# B1S.net
KiCad netlist of a schematic drawn in EasyEDA Pro
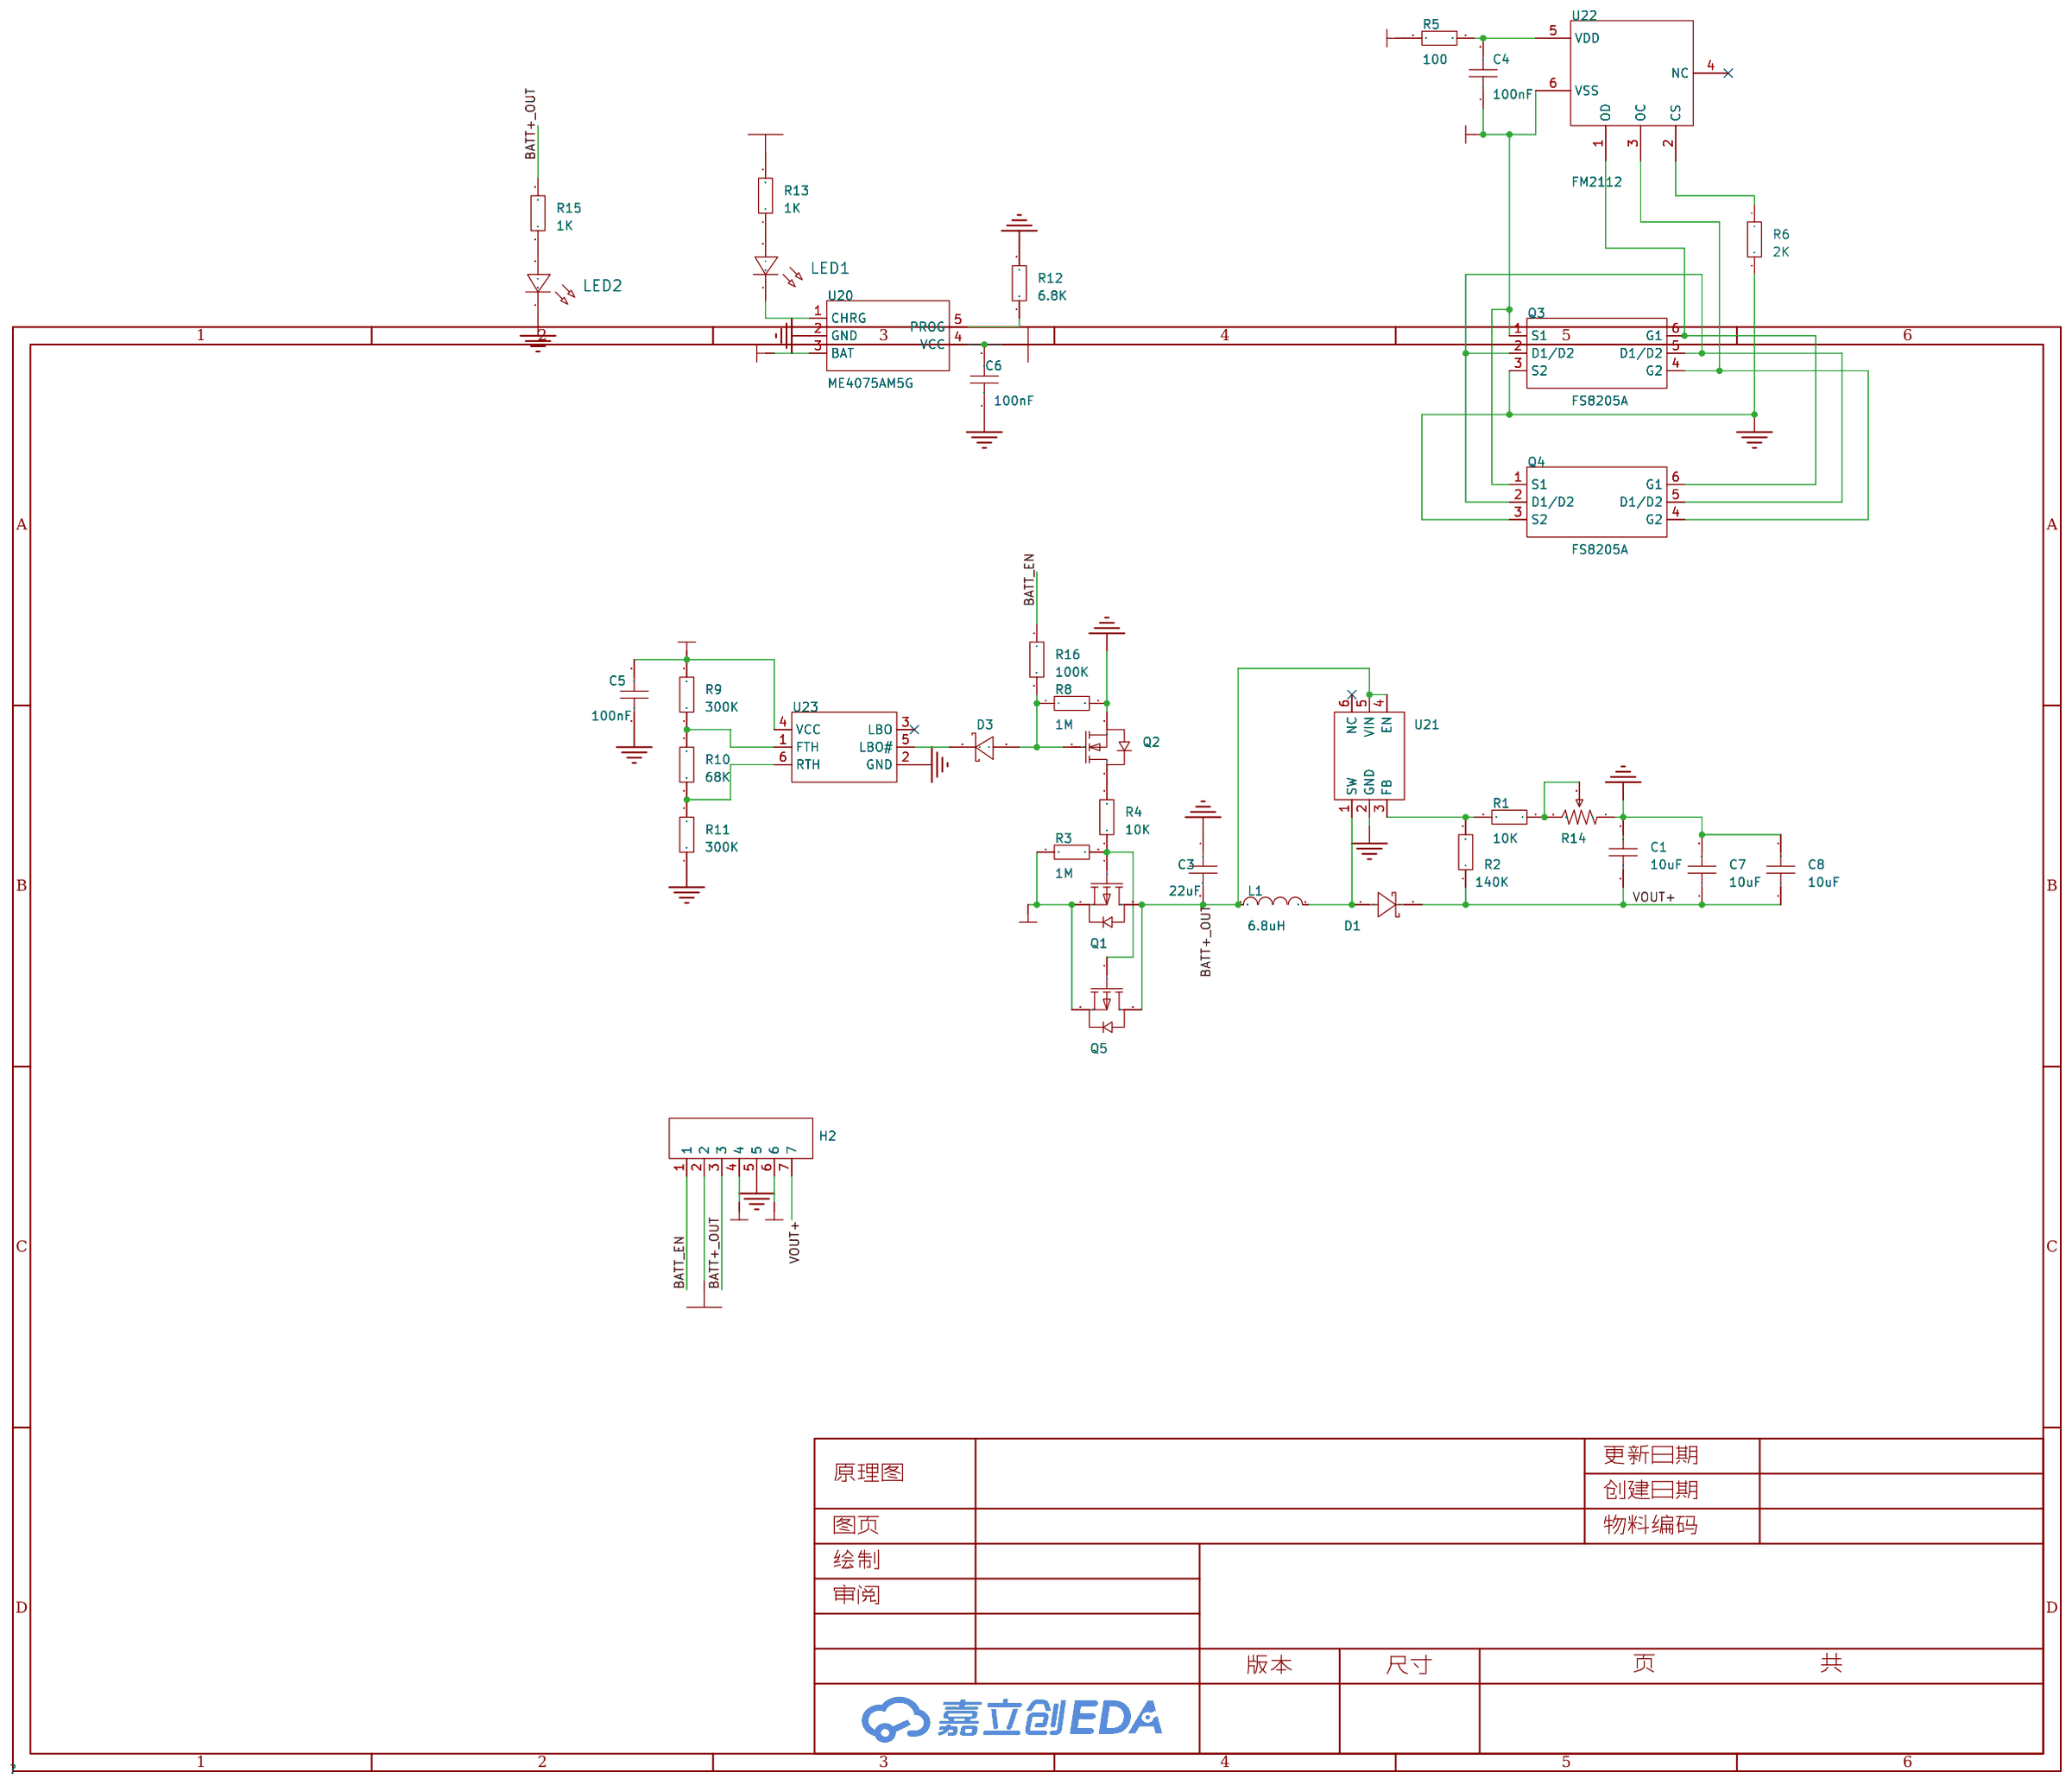
[diagram p0: schematic sheet]

(export (version "E")
  (design (tool "Eeschema 10.0.6"))
  (components
    (comp (ref "C1")
      (value "10uF")
      (footprint "easyedapro:C0805")
      (libsource (lib "easyedapro") (part "CapAcitance"))
    )
    (comp (ref "C3")
      (value "22uF")
      (footprint "easyedapro:C0805")
      (libsource (lib "easyedapro") (part "CapAcitance"))
    )
    (comp (ref "C4")
      (value "100nF")
      (footprint "easyedapro:C0805")
      (libsource (lib "easyedapro") (part "CapAcitance"))
    )
    (comp (ref "C5")
      (value "100nF")
      (footprint "easyedapro:C0805")
      (libsource (lib "easyedapro") (part "CapAcitance"))
    )
    (comp (ref "C6")
      (value "100nF")
      (footprint "easyedapro:C0805")
      (libsource (lib "easyedapro") (part "CapAcitance"))
    )
    (comp (ref "C7")
      (value "10uF")
      (footprint "easyedapro:C0805")
      (libsource (lib "easyedapro") (part "CapAcitance"))
    )
    (comp (ref "C8")
      (value "10uF")
      (footprint "easyedapro:C0805")
      (libsource (lib "easyedapro") (part "CapAcitance"))
    )
    (comp (ref "D1")
      (value "SS34")
      (footprint "easyedapro:SMA_L4.3-W2.6-LS5.0-FD")
      (description "二极管配置:独立式;正向压降(Vf):550mV@3.0A;直流反向耐压(Vr):40V;整流电流:3A;")
      (fields (field (name "Manufacturer") "R+O(宏嘉诚)"))
      (libsource (lib "easyedapro") (part "SS34_C7420365"))
    )
    (comp (ref "D3")
      (value "1N5819WS")
      (footprint "easyedapro:SOD-323_L1.8-W1.3-LS2.5-RD")
      (description "正向压降(Vf):600mV@1A;直流反向耐压(Vr):40V;整流电流:1A;")
      (fields (field (name "Manufacturer") "Hottech(合科泰)"))
      (libsource (lib "easyedapro") (part "1N5819WS"))
    )
    (comp (ref "H2")
      (value "~")
      (footprint "easyedapro:HDR-TH_7P-P2.54-V-F")
      (libsource (lib "easyedapro") (part "220S-1*7P H=8.5MM Ytype Gold-plated"))
    )
    (comp (ref "L1")
      (value "6.8uH")
      (footprint "easyedapro:IND-SMD_L7.0-W6.6")
      (description "电感值:6.8uH;精度:±20%;额定电流:5A;饱和电流(Isat):6A;类型:一体成型电感;")
      (fields (field (name "Manufacturer Part") "FXL0630-6R8-M") (field (name "Manufacturer") "cjiang(长江微电)"))
      (libsource (lib "easyedapro") (part "FXL0630-6R8-M"))
    )
    (comp (ref "LED1")
      (value "~")
      (footprint "easyedapro:LED_0603")
      (libsource (lib "easyedapro") (part "LED_R"))
    )
    (comp (ref "LED2")
      (value "~")
      (footprint "easyedapro:LED_0603")
      (libsource (lib "easyedapro") (part "LED_R"))
    )
    (comp (ref "Q1")
      (value "SI2305CDS-T1-GE3")
      (footprint "easyedapro:SOT-23-3_L2.9-W1.3-P1.90-LS2.4-BR")
      (fields (field (name "Manufacturer") "VISHAY(威世)"))
      (libsource (lib "easyedapro") (part "SI2305CDS-T1-GE3"))
    )
    (comp (ref "Q2")
      (value "SI2302")
      (footprint "easyedapro:SOT-23-3_L2.9-W1.3-P1.90-LS2.4-BR")
      (description "数量:1个N沟道;漏源电压(Vdss):20V;连续漏极电流(Id):3A;导通电阻(RDS(on)):65mΩ@2.5V;耗散功率(Pd):1W;阈值电压(Vgs(th)):1V@250uA;")
      (fields (field (name "Manufacturer") "YONGYUTAI(永裕泰)"))
      (libsource (lib "easyedapro") (part "SI2302_C2891732"))
    )
    (comp (ref "Q3")
      (value "FS8205A")
      (footprint "easyedapro:SOT-23-6_L2.9-W1.6-P0.95-LS2.8-BR")
      (description "类型:2个N沟道;漏源电压(Vdss):20V;连续漏极电流(Id):6A;导通电阻(RDS(on)):18mΩ@4.5V,6A;耗散功率(Pd):1.5W;阈值电压(Vgs(th)):1.2V;")
      (fields (field (name "Manufacturer") "FUXINSEMI(富芯森美)"))
      (libsource (lib "easyedapro") (part "FS8205A_C908265"))
    )
    (comp (ref "Q4")
      (value "FS8205A")
      (footprint "easyedapro:SOT-23-6_L2.9-W1.6-P0.95-LS2.8-BR")
      (description "类型:2个N沟道;漏源电压(Vdss):20V;连续漏极电流(Id):6A;导通电阻(RDS(on)):18mΩ@4.5V,6A;耗散功率(Pd):1.5W;阈值电压(Vgs(th)):1.2V;")
      (fields (field (name "Manufacturer") "FUXINSEMI(富芯森美)"))
      (libsource (lib "easyedapro") (part "FS8205A_C908265"))
    )
    (comp (ref "Q5")
      (value "SI2305CDS-T1-GE3")
      (footprint "easyedapro:SOT-23-3_L2.9-W1.3-P1.90-LS2.4-BR")
      (fields (field (name "Manufacturer") "VISHAY(威世)"))
      (libsource (lib "easyedapro") (part "SI2305CDS-T1-GE3"))
    )
    (comp (ref "R1") (value "10K") (footprint "easyedapro:R0603") (libsource (lib "easyedapro") (part "电阻")))
    (comp (ref "R2") (value "140K") (footprint "easyedapro:R0603") (libsource (lib "easyedapro") (part "电阻")))
    (comp (ref "R3") (value "1M") (footprint "easyedapro:R0603") (libsource (lib "easyedapro") (part "电阻")))
    (comp (ref "R4") (value "10K") (footprint "easyedapro:R0603") (libsource (lib "easyedapro") (part "电阻")))
    (comp (ref "R5") (value "100") (footprint "easyedapro:R0603") (libsource (lib "easyedapro") (part "电阻")))
    (comp (ref "R6") (value "2K") (footprint "easyedapro:R0603") (libsource (lib "easyedapro") (part "电阻")))
    (comp (ref "R8") (value "1M") (footprint "easyedapro:R0603") (libsource (lib "easyedapro") (part "电阻")))
    (comp (ref "R9") (value "300K") (footprint "easyedapro:R0603") (libsource (lib "easyedapro") (part "电阻")))
    (comp (ref "R10") (value "68K") (footprint "easyedapro:R0603") (libsource (lib "easyedapro") (part "电阻")))
    (comp (ref "R11")
      (value "300K")
      (footprint "easyedapro:R0603")
      (libsource (lib "easyedapro") (part "电阻"))
    )
    (comp (ref "R12")
      (value "6.8K")
      (footprint "easyedapro:R0603")
      (libsource (lib "easyedapro") (part "电阻"))
    )
    (comp (ref "R13") (value "1K") (footprint "easyedapro:R0603") (libsource (lib "easyedapro") (part "电阻")))
    (comp (ref "R14")
      (value "500kΩ")
      (footprint "easyedapro:RES-ADJ-SMD_JER33X-1-14")
      (description "阻值:500kΩ;精度:±25%;功率:150mW;温度系数:±250ppm/°C;")
      (fields (field (name "Manufacturer Part") "JER33X-1-55") (field (name "Manufacturer") "JIERR(捷而瑞)"))
      (libsource (lib "easyedapro") (part "JER33X-1-55"))
    )
    (comp (ref "R15") (value "1K") (footprint "easyedapro:R0603") (libsource (lib "easyedapro") (part "电阻")))
    (comp (ref "R16")
      (value "100K")
      (footprint "easyedapro:R0603")
      (libsource (lib "easyedapro") (part "电阻"))
    )
    (comp (ref "U20")
      (value "ME4075AM5G")
      (footprint "easyedapro:SOT-23-5_L2.9-W1.6-P0.95-LS2.8-BL")
      (fields (field (name "Manufacturer") "MICRONE(南京微盟)"))
      (libsource (lib "easyedapro") (part "ME4075AM5G"))
    )
    (comp (ref "U21")
      (value "SX1308")
      (footprint "easyedapro:SOT-23-6_L2.9-W1.6-P0.95-LS2.8-BL")
      (description "功能类型:升压型;输出类型:可调;工作电压:2V~24V;输出电压:28V;输出电流:2A;")
      (fields (field (name "Manufacturer") "SX(硕芯科技)"))
      (libsource (lib "easyedapro") (part "SX1308"))
    )
    (comp (ref "U22")
      (value "FM2112")
      (footprint "easyedapro:SOT-23-6_L2.9-W1.6-P0.95-LS2.8-BL")
      (fields (field (name "Manufacturer") "FM(富满)"))
      (libsource (lib "easyedapro") (part "FM2112"))
    )
    (comp (ref "U23")
      (value "CN312")
      (footprint "easyedapro:SOT-23-6_L2.9-W1.6-P0.95-LS2.8-BL")
      (description "集成电路")
      (fields (field (name "Manufacturer") "CONSONANCE(上海如韵)"))
      (libsource (lib "easyedapro") (part "CN312"))
    )
  )
  (nets
    (net (code "1") (name "/BATT+_OUT") (class "Default")
      (node (ref "C3") (pin "2") (pinfunction "2_2") (pintype "input"))
      (node (ref "H2") (pin "3") (pinfunction "3_3") (pintype "unspecified"))
      (node (ref "L1") (pin "1") (pinfunction "1_1") (pintype "unspecified"))
      (node (ref "Q1") (pin "3") (pinfunction "D_3") (pintype "unspecified"))
      (node (ref "Q5") (pin "3") (pinfunction "D_3") (pintype "unspecified"))
      (node (ref "R15") (pin "2") (pinfunction "2_2") (pintype "input"))
      (node (ref "U21") (pin "4") (pinfunction "EN_4") (pintype "unspecified"))
      (node (ref "U21") (pin "5") (pinfunction "VIN_5") (pintype "unspecified"))
    )
    (net (code "2") (name "/BATT_EN") (class "Default")
      (node (ref "H2") (pin "1") (pinfunction "1_1") (pintype "unspecified"))
      (node (ref "R16") (pin "1") (pinfunction "1_1") (pintype "input"))
    )
    (net (code "3") (name "/VOUT+") (class "Default")
      (node (ref "C1") (pin "1") (pinfunction "1_1") (pintype "input"))
      (node (ref "C7") (pin "1") (pinfunction "1_1") (pintype "input"))
      (node (ref "C8") (pin "1") (pinfunction "1_1") (pintype "input"))
      (node (ref "D1") (pin "2") (pinfunction "K_2") (pintype "unspecified"))
      (node (ref "H2") (pin "7") (pinfunction "7_7") (pintype "unspecified"))
      (node (ref "R2") (pin "1") (pinfunction "1_1") (pintype "input"))
    )
    (net (code "4") (name "BATT+") (class "Default")
      (node (ref "C5") (pin "2") (pinfunction "2_2") (pintype "input"))
      (node (ref "H2") (pin "4") (pinfunction "4_4") (pintype "unspecified"))
      (node (ref "Q1") (pin "2") (pinfunction "S_2") (pintype "unspecified"))
      (node (ref "Q5") (pin "2") (pinfunction "S_2") (pintype "unspecified"))
      (node (ref "R3") (pin "1") (pinfunction "1_1") (pintype "input"))
      (node (ref "R5") (pin "2") (pinfunction "2_2") (pintype "input"))
      (node (ref "R9") (pin "2") (pinfunction "2_2") (pintype "input"))
      (node (ref "U20") (pin "3") (pinfunction "BAT_3") (pintype "unspecified"))
      (node (ref "U23") (pin "4") (pinfunction "VCC_4") (pintype "unspecified"))
    )
    (net (code "5") (name "BATT-") (class "Default")
      (node (ref "C4") (pin "1") (pinfunction "1_1") (pintype "input"))
      (node (ref "H2") (pin "6") (pinfunction "6_6") (pintype "unspecified"))
      (node (ref "Q3") (pin "1") (pinfunction "S1_1") (pintype "unspecified"))
      (node (ref "Q4") (pin "1") (pinfunction "S1_1") (pintype "unspecified"))
      (node (ref "U22") (pin "6") (pinfunction "VSS_6") (pintype "unspecified"))
    )
    (net (code "6") (name "CHG+") (class "Default")
      (node (ref "C6") (pin "2") (pinfunction "2_2") (pintype "input"))
      (node (ref "H2") (pin "2") (pinfunction "2_2") (pintype "unspecified"))
      (node (ref "R13") (pin "2") (pinfunction "2_2") (pintype "input"))
      (node (ref "U20") (pin "4") (pinfunction "VCC_4") (pintype "unspecified"))
    )
    (net (code "7") (name "GND") (class "Default")
      (node (ref "C1") (pin "2") (pinfunction "2_2") (pintype "input"))
      (node (ref "C3") (pin "1") (pinfunction "1_1") (pintype "input"))
      (node (ref "C5") (pin "1") (pinfunction "1_1") (pintype "input"))
      (node (ref "C6") (pin "1") (pinfunction "1_1") (pintype "input"))
      (node (ref "C7") (pin "2") (pinfunction "2_2") (pintype "input"))
      (node (ref "C8") (pin "2") (pinfunction "2_2") (pintype "input"))
      (node (ref "H2") (pin "5") (pinfunction "5_5") (pintype "unspecified"))
      (node (ref "LED2") (pin "1") (pinfunction "C_1") (pintype "input"))
      (node (ref "Q2") (pin "2") (pinfunction "S_2") (pintype "unspecified"))
      (node (ref "Q3") (pin "3") (pinfunction "S2_3") (pintype "unspecified"))
      (node (ref "Q4") (pin "3") (pinfunction "S2_3") (pintype "unspecified"))
      (node (ref "R11") (pin "1") (pinfunction "1_1") (pintype "input"))
      (node (ref "R12") (pin "2") (pinfunction "2_2") (pintype "input"))
      (node (ref "R14") (pin "1") (pinfunction "1_1") (pintype "unspecified"))
      (node (ref "R6") (pin "2") (pinfunction "2_2") (pintype "input"))
      (node (ref "R8") (pin "2") (pinfunction "2_2") (pintype "input"))
      (node (ref "U20") (pin "2") (pinfunction "GND_2") (pintype "unspecified"))
      (node (ref "U21") (pin "2") (pinfunction "GND_2") (pintype "unspecified"))
      (node (ref "U23") (pin "2") (pinfunction "GND_2") (pintype "unspecified"))
    )
    (net (code "8") (name "Net-(D1-A)") (class "Default")
      (node (ref "D1") (pin "1") (pinfunction "A_1") (pintype "unspecified"))
      (node (ref "L1") (pin "2") (pinfunction "2_2") (pintype "unspecified"))
      (node (ref "U21") (pin "1") (pinfunction "SW_1") (pintype "unspecified"))
    )
    (net (code "9") (name "Net-(D3-A)") (class "Default")
      (node (ref "D3") (pin "2") (pinfunction "A_2") (pintype "unspecified"))
      (node (ref "Q2") (pin "1") (pinfunction "G_1") (pintype "unspecified"))
      (node (ref "R16") (pin "2") (pinfunction "2_2") (pintype "input"))
      (node (ref "R8") (pin "1") (pinfunction "1_1") (pintype "input"))
    )
    (net (code "10") (name "Net-(D3-K)") (class "Default")
      (node (ref "D3") (pin "1") (pinfunction "K_1") (pintype "unspecified"))
      (node (ref "U23") (pin "5") (pinfunction "LBO#_5") (pintype "unspecified"))
    )
    (net (code "11") (name "Net-(LED1-A)") (class "Default")
      (node (ref "LED1") (pin "2") (pinfunction "A_2") (pintype "input"))
      (node (ref "R13") (pin "1") (pinfunction "1_1") (pintype "input"))
    )
    (net (code "12") (name "Net-(LED1-C)") (class "Default")
      (node (ref "LED1") (pin "1") (pinfunction "C_1") (pintype "input"))
      (node (ref "U20") (pin "1") (pinfunction "CHRG_1") (pintype "unspecified"))
    )
    (net (code "13") (name "Net-(LED2-A)") (class "Default")
      (node (ref "LED2") (pin "2") (pinfunction "A_2") (pintype "input"))
      (node (ref "R15") (pin "1") (pinfunction "1_1") (pintype "input"))
    )
    (net (code "14") (name "Net-(Q1-G)") (class "Default")
      (node (ref "Q1") (pin "1") (pinfunction "G_1") (pintype "unspecified"))
      (node (ref "Q5") (pin "1") (pinfunction "G_1") (pintype "unspecified"))
      (node (ref "R3") (pin "2") (pinfunction "2_2") (pintype "input"))
      (node (ref "R4") (pin "1") (pinfunction "1_1") (pintype "input"))
    )
    (net (code "15") (name "Net-(Q2-D)") (class "Default")
      (node (ref "Q2") (pin "3") (pinfunction "D_3") (pintype "unspecified"))
      (node (ref "R4") (pin "2") (pinfunction "2_2") (pintype "input"))
    )
    (net (code "16") (name "Net-(Q3-D1{slash}D2-Pad2)") (class "Default")
      (node (ref "Q3") (pin "2") (pinfunction "D1/D2_2") (pintype "unspecified"))
      (node (ref "Q3") (pin "5") (pinfunction "D1/D2_5") (pintype "unspecified"))
      (node (ref "Q4") (pin "2") (pinfunction "D1/D2_2") (pintype "unspecified"))
      (node (ref "Q4") (pin "5") (pinfunction "D1/D2_5") (pintype "unspecified"))
    )
    (net (code "17") (name "Net-(Q3-G1)") (class "Default")
      (node (ref "Q3") (pin "6") (pinfunction "G1_6") (pintype "unspecified"))
      (node (ref "Q4") (pin "6") (pinfunction "G1_6") (pintype "unspecified"))
      (node (ref "U22") (pin "1") (pinfunction "OD_1") (pintype "unspecified"))
    )
    (net (code "18") (name "Net-(Q3-G2)") (class "Default")
      (node (ref "Q3") (pin "4") (pinfunction "G2_4") (pintype "unspecified"))
      (node (ref "Q4") (pin "4") (pinfunction "G2_4") (pintype "unspecified"))
      (node (ref "U22") (pin "3") (pinfunction "OC_3") (pintype "unspecified"))
    )
    (net (code "19") (name "Net-(R1-Pad1)") (class "Default")
      (node (ref "R1") (pin "1") (pinfunction "1_1") (pintype "input"))
      (node (ref "R14") (pin "2") (pinfunction "2_2") (pintype "unspecified"))
      (node (ref "R14") (pin "3") (pinfunction "3_3") (pintype "unspecified"))
    )
    (net (code "20") (name "Net-(U20-PROG)") (class "Default")
      (node (ref "R12") (pin "1") (pinfunction "1_1") (pintype "input"))
      (node (ref "U20") (pin "5") (pinfunction "PROG_5") (pintype "unspecified"))
    )
    (net (code "21") (name "Net-(U21-FB)") (class "Default")
      (node (ref "R1") (pin "2") (pinfunction "2_2") (pintype "input"))
      (node (ref "R2") (pin "2") (pinfunction "2_2") (pintype "input"))
      (node (ref "U21") (pin "3") (pinfunction "FB_3") (pintype "unspecified"))
    )
    (net (code "22") (name "Net-(U22-CS)") (class "Default")
      (node (ref "R6") (pin "1") (pinfunction "1_1") (pintype "input"))
      (node (ref "U22") (pin "2") (pinfunction "CS_2") (pintype "unspecified"))
    )
    (net (code "23") (name "Net-(U22-VDD)") (class "Default")
      (node (ref "C4") (pin "2") (pinfunction "2_2") (pintype "input"))
      (node (ref "R5") (pin "1") (pinfunction "1_1") (pintype "input"))
      (node (ref "U22") (pin "5") (pinfunction "VDD_5") (pintype "unspecified"))
    )
    (net (code "24") (name "Net-(U23-FTH)") (class "Default")
      (node (ref "R10") (pin "2") (pinfunction "2_2") (pintype "input"))
      (node (ref "R9") (pin "1") (pinfunction "1_1") (pintype "input"))
      (node (ref "U23") (pin "1") (pinfunction "FTH_1") (pintype "unspecified"))
    )
    (net (code "25") (name "Net-(U23-RTH)") (class "Default")
      (node (ref "R10") (pin "1") (pinfunction "1_1") (pintype "input"))
      (node (ref "R11") (pin "2") (pinfunction "2_2") (pintype "input"))
      (node (ref "U23") (pin "6") (pinfunction "RTH_6") (pintype "unspecified"))
    )
    (net (code "26") (name "unconnected-(U21-NC-Pad6)") (class "Default")
      (node (ref "U21") (pin "6") (pinfunction "NC_6") (pintype "unspecified+no_connect"))
    )
    (net (code "27") (name "unconnected-(U22-NC-Pad4)") (class "Default")
      (node (ref "U22") (pin "4") (pinfunction "NC_4") (pintype "unspecified+no_connect"))
    )
    (net (code "28") (name "unconnected-(U23-LBO-Pad3)") (class "Default")
      (node (ref "U23") (pin "3") (pinfunction "LBO_3") (pintype "unspecified+no_connect"))
    )
  )
)
